# SensorController.net
KiCad netlist of a schematic drawn in EAGLE
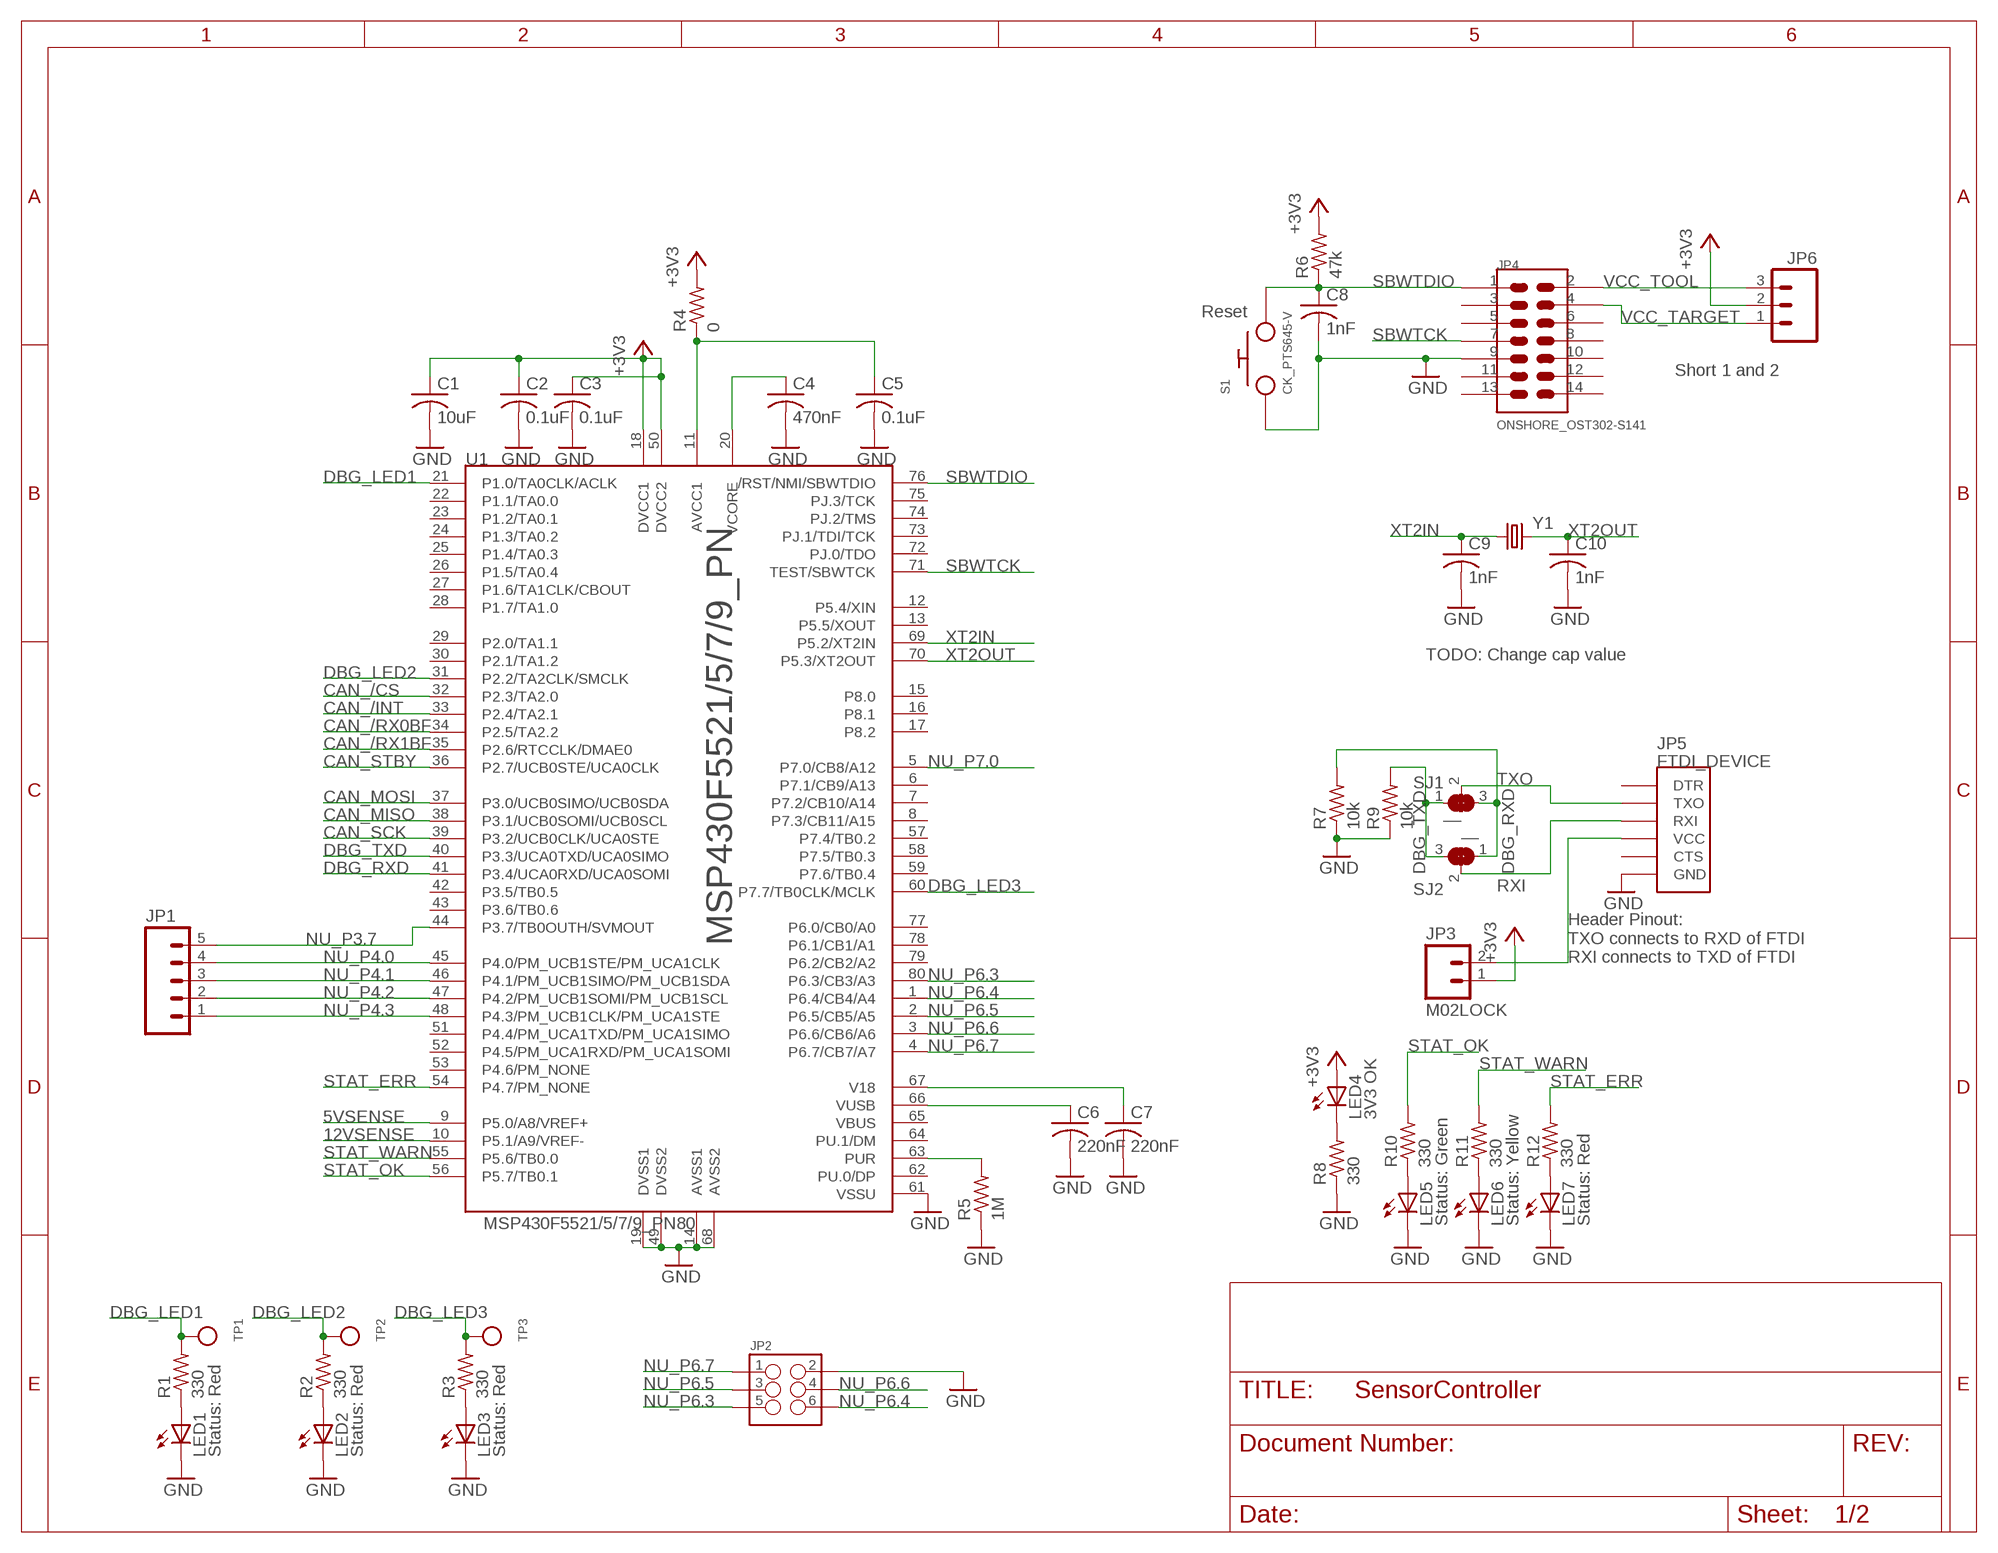
[diagram p0: schematic, sheet 1]
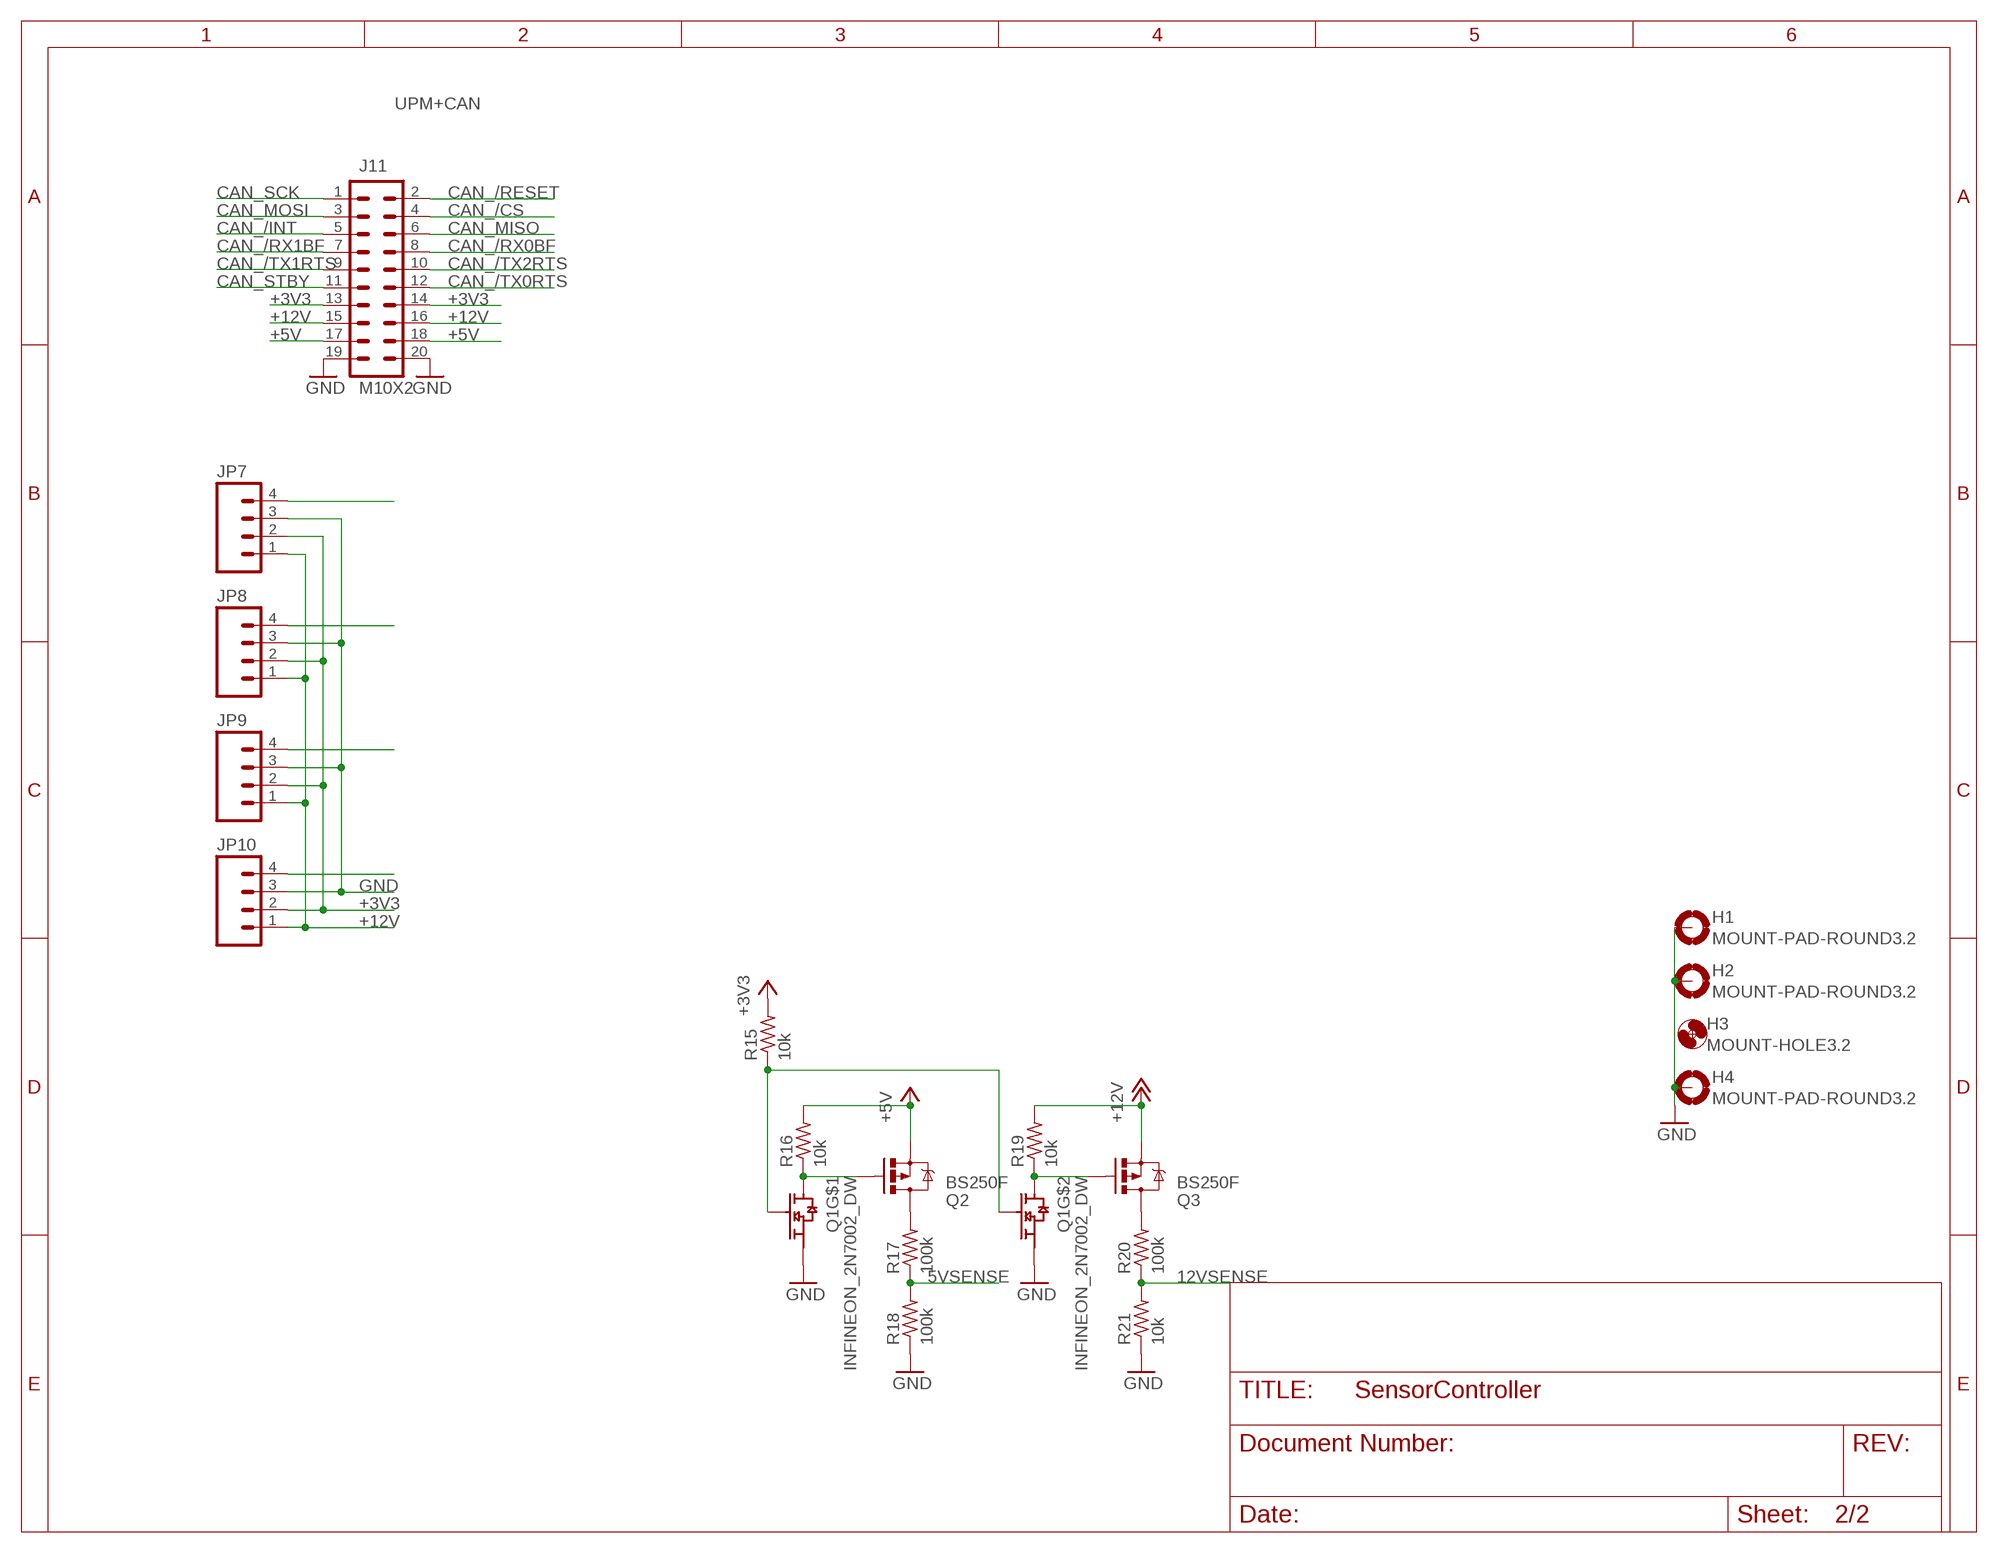
[diagram p1: schematic, sheet 2]

(export (version "E")
  (design (tool "Eeschema 10.0.6"))
  (components
    (comp (ref "H1")
      (value "MOUNT-PAD-ROUND3.2")
      (footprint "eagle-import:3,2-PAD")
      (libsource (lib "eagle-import") (part "MOUNT-PAD-ROUND3.2"))
    )
    (comp (ref "H2")
      (value "MOUNT-PAD-ROUND3.2")
      (footprint "eagle-import:3,2-PAD")
      (libsource (lib "eagle-import") (part "MOUNT-PAD-ROUND3.2"))
    )
    (comp (ref "H3")
      (value "MOUNT-HOLE3.2")
      (footprint "eagle-import:3,2")
      (libsource (lib "eagle-import") (part "MOUNT-HOLE3.2"))
    )
    (comp (ref "H4")
      (value "MOUNT-PAD-ROUND3.2")
      (footprint "eagle-import:3,2-PAD")
      (libsource (lib "eagle-import") (part "MOUNT-PAD-ROUND3.2"))
    )
    (comp (ref "J11")
      (value "M10X2")
      (footprint "eagle-import:2X10")
      (libsource (lib "eagle-import") (part "M10X2"))
    )
    (comp (ref "JP7")
      (value "M04PTH")
      (footprint "eagle-import:1X04")
      (libsource (lib "eagle-import") (part "M04PTH"))
    )
    (comp (ref "JP8")
      (value "M04PTH")
      (footprint "eagle-import:1X04")
      (libsource (lib "eagle-import") (part "M04PTH"))
    )
    (comp (ref "JP9")
      (value "M04PTH")
      (footprint "eagle-import:1X04")
      (libsource (lib "eagle-import") (part "M04PTH"))
    )
    (comp (ref "JP10")
      (value "M04PTH")
      (footprint "eagle-import:1X04")
      (libsource (lib "eagle-import") (part "M04PTH"))
    )
    (comp (ref "Q1")
      (value "INFINEON_2N7002_DW")
      (footprint "eagle-import:INFINEON_SOT363")
      (libsource (lib "eagle-import") (part "INFINEON_2N7002_DW"))
    )
    (comp (ref "Q2")
      (value "BS250F")
      (footprint "eagle-import:SOT23-3")
      (libsource (lib "eagle-import") (part "MOSFET-PCHANNELSMD"))
    )
    (comp (ref "Q3")
      (value "BS250F")
      (footprint "eagle-import:SOT23-3")
      (libsource (lib "eagle-import") (part "MOSFET-PCHANNELSMD"))
    )
    (comp (ref "R15")
      (value "10k")
      (footprint "eagle-import:R0603")
      (libsource (lib "eagle-import") (part "R-US_R0603"))
    )
    (comp (ref "R16")
      (value "10k")
      (footprint "eagle-import:R0603")
      (libsource (lib "eagle-import") (part "R-US_R0603"))
    )
    (comp (ref "R17")
      (value "100k")
      (footprint "eagle-import:R0603")
      (libsource (lib "eagle-import") (part "R-US_R0603"))
    )
    (comp (ref "R18")
      (value "100k")
      (footprint "eagle-import:R0603")
      (libsource (lib "eagle-import") (part "R-US_R0603"))
    )
    (comp (ref "R19")
      (value "10k")
      (footprint "eagle-import:R0603")
      (libsource (lib "eagle-import") (part "R-US_R0603"))
    )
    (comp (ref "R20")
      (value "100k")
      (footprint "eagle-import:R0603")
      (libsource (lib "eagle-import") (part "R-US_R0603"))
    )
    (comp (ref "R21")
      (value "10k")
      (footprint "eagle-import:R0603")
      (libsource (lib "eagle-import") (part "R-US_R0603"))
    )
    (comp (ref "C1")
      (value "10uF")
      (footprint "eagle-import:C0805")
      (libsource (lib "eagle-import") (part "C-USC0805"))
    )
    (comp (ref "C2")
      (value "0.1uF")
      (footprint "eagle-import:C0603")
      (libsource (lib "eagle-import") (part "C-USC0603"))
    )
    (comp (ref "C3")
      (value "0.1uF")
      (footprint "eagle-import:C0603")
      (libsource (lib "eagle-import") (part "C-USC0603"))
    )
    (comp (ref "C4")
      (value "470nF")
      (footprint "eagle-import:C0603")
      (libsource (lib "eagle-import") (part "C-USC0603"))
    )
    (comp (ref "C5")
      (value "0.1uF")
      (footprint "eagle-import:C0603")
      (libsource (lib "eagle-import") (part "C-USC0603"))
    )
    (comp (ref "C6")
      (value "220nF")
      (footprint "eagle-import:C0603")
      (libsource (lib "eagle-import") (part "C-USC0603"))
    )
    (comp (ref "C7")
      (value "220nF")
      (footprint "eagle-import:C0603")
      (libsource (lib "eagle-import") (part "C-USC0603"))
    )
    (comp (ref "C8")
      (value "1nF")
      (footprint "eagle-import:C0603")
      (libsource (lib "eagle-import") (part "C-USC0603"))
    )
    (comp (ref "C9")
      (value "1nF")
      (footprint "eagle-import:C0603")
      (libsource (lib "eagle-import") (part "C-USC0603"))
    )
    (comp (ref "C10")
      (value "1nF")
      (footprint "eagle-import:C0603")
      (libsource (lib "eagle-import") (part "C-USC0603"))
    )
    (comp (ref "JP1")
      (value "M05PTH")
      (footprint "eagle-import:1X05")
      (libsource (lib "eagle-import") (part "M05PTH"))
    )
    (comp (ref "JP2")
      (value "M03X22X3_SILK_SM")
      (footprint "eagle-import:2X3")
      (libsource (lib "eagle-import") (part "M03X22X3_SILK_SM"))
    )
    (comp (ref "JP3")
      (value "M02LOCK")
      (footprint "eagle-import:1X02_LOCK")
      (libsource (lib "eagle-import") (part "M02LOCK"))
    )
    (comp (ref "JP4")
      (value "ONSHORE_OST302-S141")
      (footprint "eagle-import:ONSHORE_OST302-S141")
      (libsource (lib "eagle-import") (part "ONSHORE_OST302-S141"))
    )
    (comp (ref "JP5")
      (value "FTDI_DEVICE")
      (footprint "eagle-import:FTDI_DEVICE_SIDE")
      (libsource (lib "eagle-import") (part "FTDI_DEVICE"))
    )
    (comp (ref "JP6")
      (value "M03LOCK")
      (footprint "eagle-import:1X03_LOCK")
      (libsource (lib "eagle-import") (part "M03LOCK"))
    )
    (comp (ref "LED1")
      (value "Status: Red")
      (footprint "eagle-import:LED-0603")
      (libsource (lib "eagle-import") (part "LED0603"))
    )
    (comp (ref "LED2")
      (value "Status: Red")
      (footprint "eagle-import:LED-0603")
      (libsource (lib "eagle-import") (part "LED0603"))
    )
    (comp (ref "LED3")
      (value "Status: Red")
      (footprint "eagle-import:LED-0603")
      (libsource (lib "eagle-import") (part "LED0603"))
    )
    (comp (ref "LED4")
      (value "3V3 OK")
      (footprint "eagle-import:LED-0603")
      (libsource (lib "eagle-import") (part "LED0603"))
    )
    (comp (ref "LED5")
      (value "Status: Green")
      (footprint "eagle-import:LED-0603")
      (libsource (lib "eagle-import") (part "LED0603"))
    )
    (comp (ref "LED6")
      (value "Status: Yellow")
      (footprint "eagle-import:LED-0603")
      (libsource (lib "eagle-import") (part "LED0603"))
    )
    (comp (ref "LED7")
      (value "Status: Red")
      (footprint "eagle-import:LED-0603")
      (libsource (lib "eagle-import") (part "LED0603"))
    )
    (comp (ref "R1")
      (value "330")
      (footprint "eagle-import:R0603")
      (libsource (lib "eagle-import") (part "R-US_R0603"))
    )
    (comp (ref "R2")
      (value "330")
      (footprint "eagle-import:R0603")
      (libsource (lib "eagle-import") (part "R-US_R0603"))
    )
    (comp (ref "R3")
      (value "330")
      (footprint "eagle-import:R0603")
      (libsource (lib "eagle-import") (part "R-US_R0603"))
    )
    (comp (ref "R4")
      (value "0")
      (footprint "eagle-import:R0603")
      (libsource (lib "eagle-import") (part "R-US_R0603"))
    )
    (comp (ref "R5")
      (value "1M")
      (footprint "eagle-import:R0603")
      (libsource (lib "eagle-import") (part "R-US_R0603"))
    )
    (comp (ref "R6")
      (value "47k")
      (footprint "eagle-import:R0603")
      (libsource (lib "eagle-import") (part "R-US_R0603"))
    )
    (comp (ref "R7")
      (value "10k")
      (footprint "eagle-import:R0603")
      (libsource (lib "eagle-import") (part "R-US_R0603"))
    )
    (comp (ref "R8")
      (value "330")
      (footprint "eagle-import:R0603")
      (libsource (lib "eagle-import") (part "R-US_R0603"))
    )
    (comp (ref "R9")
      (value "10k")
      (footprint "eagle-import:R0603")
      (libsource (lib "eagle-import") (part "R-US_R0603"))
    )
    (comp (ref "R10")
      (value "330")
      (footprint "eagle-import:R0603")
      (libsource (lib "eagle-import") (part "R-US_R0603"))
    )
    (comp (ref "R11")
      (value "330")
      (footprint "eagle-import:R0603")
      (libsource (lib "eagle-import") (part "R-US_R0603"))
    )
    (comp (ref "R12")
      (value "330")
      (footprint "eagle-import:R0603")
      (libsource (lib "eagle-import") (part "R-US_R0603"))
    )
    (comp (ref "S1")
      (value "CK_PTS645-V")
      (footprint "eagle-import:CK_PTS645-V")
      (libsource (lib "eagle-import") (part "CK_PTS645-V"))
    )
    (comp (ref "SJ1")
      (value "SOLDERJUMPER_2WAY0603")
      (footprint "eagle-import:SOLDERJUMPER_2WAY_OPEN_0603")
      (libsource (lib "eagle-import") (part "SOLDERJUMPER_2WAY0603"))
    )
    (comp (ref "SJ2")
      (value "SOLDERJUMPER_2WAY0603")
      (footprint "eagle-import:SOLDERJUMPER_2WAY_OPEN_0603")
      (libsource (lib "eagle-import") (part "SOLDERJUMPER_2WAY0603"))
    )
    (comp (ref "TP1")
      (value "TESTPOINT0.1\"")
      (footprint "eagle-import:1X01_ROUND")
      (libsource (lib "eagle-import") (part "TESTPOINT0.1{dblquote}"))
    )
    (comp (ref "TP2")
      (value "TESTPOINT0.1\"")
      (footprint "eagle-import:1X01_ROUND")
      (libsource (lib "eagle-import") (part "TESTPOINT0.1{dblquote}"))
    )
    (comp (ref "TP3")
      (value "TESTPOINT0.1\"")
      (footprint "eagle-import:1X01_ROUND")
      (libsource (lib "eagle-import") (part "TESTPOINT0.1{dblquote}"))
    )
    (comp (ref "U1")
      (value "MSP430F5521/5/7/9_PN80")
      (footprint "eagle-import:PN80")
      (libsource (lib "eagle-import") (part "MSP430F5521/5/7/9_PN80"))
    )
    (comp (ref "Y1")
      (value "CRYSTALHC49UV")
      (footprint "eagle-import:HC49U-V")
      (libsource (lib "eagle-import") (part "CRYSTALHC49UV"))
    )
  )
  (nets
    (net (code "1") (name "+3V3") (class "Default")
      (node (ref "C1") (pin "1") (pinfunction "1_1") (pintype "passive"))
      (node (ref "C2") (pin "1") (pinfunction "1_1") (pintype "passive"))
      (node (ref "C3") (pin "1") (pinfunction "1_1") (pintype "passive"))
      (node (ref "J11") (pin "13") (pinfunction "13_13") (pintype "passive"))
      (node (ref "J11") (pin "14") (pinfunction "14_14") (pintype "passive"))
      (node (ref "JP10") (pin "2") (pinfunction "2_2") (pintype "passive"))
      (node (ref "JP3") (pin "1") (pinfunction "1_1") (pintype "passive"))
      (node (ref "JP6") (pin "2") (pinfunction "2_2") (pintype "passive"))
      (node (ref "JP7") (pin "2") (pinfunction "2_2") (pintype "passive"))
      (node (ref "JP8") (pin "2") (pinfunction "2_2") (pintype "passive"))
      (node (ref "JP9") (pin "2") (pinfunction "2_2") (pintype "passive"))
      (node (ref "LED4") (pin "A") (pinfunction "A_A") (pintype "passive"))
      (node (ref "R15") (pin "2") (pinfunction "2_2") (pintype "passive"))
      (node (ref "R4") (pin "2") (pinfunction "2_2") (pintype "passive"))
      (node (ref "R6") (pin "2") (pinfunction "2_2") (pintype "passive"))
      (node (ref "U1") (pin "18") (pinfunction "DVCC1_18") (pintype "bidirectional"))
      (node (ref "U1") (pin "50") (pinfunction "DVCC2_50") (pintype "bidirectional"))
    )
    (net (code "2") (name "+5V") (class "Default")
      (node (ref "J11") (pin "17") (pinfunction "17_17") (pintype "passive"))
      (node (ref "J11") (pin "18") (pinfunction "18_18") (pintype "passive"))
      (node (ref "Q2") (pin "2") (pinfunction "S_2") (pintype "passive"))
      (node (ref "R16") (pin "2") (pinfunction "2_2") (pintype "passive"))
    )
    (net (code "3") (name "+12V") (class "Default")
      (node (ref "J11") (pin "15") (pinfunction "15_15") (pintype "passive"))
      (node (ref "J11") (pin "16") (pinfunction "16_16") (pintype "passive"))
      (node (ref "JP10") (pin "1") (pinfunction "1_1") (pintype "passive"))
      (node (ref "JP7") (pin "1") (pinfunction "1_1") (pintype "passive"))
      (node (ref "JP8") (pin "1") (pinfunction "1_1") (pintype "passive"))
      (node (ref "JP9") (pin "1") (pinfunction "1_1") (pintype "passive"))
      (node (ref "Q3") (pin "2") (pinfunction "S_2") (pintype "passive"))
      (node (ref "R19") (pin "2") (pinfunction "2_2") (pintype "passive"))
    )
    (net (code "4") (name "5VSENSE") (class "Default")
      (node (ref "R17") (pin "1") (pinfunction "1_1") (pintype "passive"))
      (node (ref "R18") (pin "2") (pinfunction "2_2") (pintype "passive"))
      (node (ref "U1") (pin "9") (pinfunction "P5.0/A8/VREF+_9") (pintype "bidirectional"))
    )
    (net (code "5") (name "12VSENSE") (class "Default")
      (node (ref "R20") (pin "1") (pinfunction "1_1") (pintype "passive"))
      (node (ref "R21") (pin "2") (pinfunction "2_2") (pintype "passive"))
      (node (ref "U1") (pin "10") (pinfunction "P5.1/A9/VREF-_10") (pintype "bidirectional"))
    )
    (net (code "6") (name "CAN_MISO") (class "Default")
      (node (ref "J11") (pin "6") (pinfunction "6_6") (pintype "passive"))
      (node (ref "U1") (pin "38") (pinfunction "P3.1/UCB0SOMI/UCB0SCL_38") (pintype "bidirectional"))
    )
    (net (code "7") (name "CAN_MOSI") (class "Default")
      (node (ref "J11") (pin "3") (pinfunction "3_3") (pintype "passive"))
      (node (ref "U1") (pin "37") (pinfunction "P3.0/UCB0SIMO/UCB0SDA_37") (pintype "bidirectional"))
    )
    (net (code "8") (name "CAN_SCK") (class "Default")
      (node (ref "J11") (pin "1") (pinfunction "1_1") (pintype "passive"))
      (node (ref "U1") (pin "39") (pinfunction "P3.2/UCB0CLK/UCA0STE_39") (pintype "bidirectional"))
    )
    (net (code "9") (name "CAN_STBY") (class "Default")
      (node (ref "J11") (pin "11") (pinfunction "11_11") (pintype "passive"))
      (node (ref "U1") (pin "36") (pinfunction "P2.7/UCB0STE/UCA0CLK_36") (pintype "bidirectional"))
    )
    (net (code "10") (name "CAN_{slash}CS") (class "Default")
      (node (ref "J11") (pin "4") (pinfunction "4_4") (pintype "passive"))
      (node (ref "U1") (pin "32") (pinfunction "P2.3/TA2.0_32") (pintype "bidirectional"))
    )
    (net (code "11") (name "CAN_{slash}INT") (class "Default")
      (node (ref "J11") (pin "5") (pinfunction "5_5") (pintype "passive"))
      (node (ref "U1") (pin "33") (pinfunction "P2.4/TA2.1_33") (pintype "bidirectional"))
    )
    (net (code "12") (name "CAN_{slash}RESET") (class "Default")
      (node (ref "J11") (pin "2") (pinfunction "2_2") (pintype "passive"))
    )
    (net (code "13") (name "CAN_{slash}RX0BF") (class "Default")
      (node (ref "J11") (pin "8") (pinfunction "8_8") (pintype "passive"))
      (node (ref "U1") (pin "34") (pinfunction "P2.5/TA2.2_34") (pintype "bidirectional"))
    )
    (net (code "14") (name "CAN_{slash}RX1BF") (class "Default")
      (node (ref "J11") (pin "7") (pinfunction "7_7") (pintype "passive"))
      (node (ref "U1") (pin "35") (pinfunction "P2.6/RTCCLK/DMAE0_35") (pintype "bidirectional"))
    )
    (net (code "15") (name "CAN_{slash}TX0RTS") (class "Default")
      (node (ref "J11") (pin "12") (pinfunction "12_12") (pintype "passive"))
    )
    (net (code "16") (name "CAN_{slash}TX1RTS") (class "Default")
      (node (ref "J11") (pin "9") (pinfunction "9_9") (pintype "passive"))
    )
    (net (code "17") (name "CAN_{slash}TX2RTS") (class "Default")
      (node (ref "J11") (pin "10") (pinfunction "10_10") (pintype "passive"))
    )
    (net (code "18") (name "DBG_LED1") (class "Default")
      (node (ref "R1") (pin "2") (pinfunction "2_2") (pintype "passive"))
      (node (ref "TP1") (pin "1") (pinfunction "P$1_1") (pintype "bidirectional"))
      (node (ref "U1") (pin "21") (pinfunction "P1.0/TA0CLK/ACLK_21") (pintype "bidirectional"))
    )
    (net (code "19") (name "DBG_LED2") (class "Default")
      (node (ref "R2") (pin "2") (pinfunction "2_2") (pintype "passive"))
      (node (ref "TP2") (pin "1") (pinfunction "P$1_1") (pintype "bidirectional"))
      (node (ref "U1") (pin "31") (pinfunction "P2.2/TA2CLK/SMCLK_31") (pintype "bidirectional"))
    )
    (net (code "20") (name "DBG_LED3") (class "Default")
      (node (ref "R3") (pin "2") (pinfunction "2_2") (pintype "passive"))
      (node (ref "TP3") (pin "1") (pinfunction "P$1_1") (pintype "bidirectional"))
      (node (ref "U1") (pin "60") (pinfunction "P7.7/TB0CLK/MCLK_60") (pintype "bidirectional"))
    )
    (net (code "21") (name "DBG_RXD") (class "Default")
      (node (ref "R7") (pin "2") (pinfunction "2_2") (pintype "passive"))
      (node (ref "SJ1") (pin "3") (pinfunction "3_3") (pintype "passive"))
      (node (ref "SJ2") (pin "1") (pinfunction "1_1") (pintype "passive"))
      (node (ref "U1") (pin "41") (pinfunction "P3.4/UCA0RXD/UCA0SOMI_41") (pintype "bidirectional"))
    )
    (net (code "22") (name "DBG_TXD") (class "Default")
      (node (ref "R9") (pin "2") (pinfunction "2_2") (pintype "passive"))
      (node (ref "SJ1") (pin "1") (pinfunction "1_1") (pintype "passive"))
      (node (ref "SJ2") (pin "3") (pinfunction "3_3") (pintype "passive"))
      (node (ref "U1") (pin "40") (pinfunction "P3.3/UCA0TXD/UCA0SIMO_40") (pintype "bidirectional"))
    )
    (net (code "23") (name "GND") (class "Default")
      (node (ref "C1") (pin "2") (pinfunction "2_2") (pintype "passive"))
      (node (ref "C10") (pin "2") (pinfunction "2_2") (pintype "passive"))
      (node (ref "C2") (pin "2") (pinfunction "2_2") (pintype "passive"))
      (node (ref "C3") (pin "2") (pinfunction "2_2") (pintype "passive"))
      (node (ref "C4") (pin "2") (pinfunction "2_2") (pintype "passive"))
      (node (ref "C5") (pin "2") (pinfunction "2_2") (pintype "passive"))
      (node (ref "C6") (pin "2") (pinfunction "2_2") (pintype "passive"))
      (node (ref "C7") (pin "2") (pinfunction "2_2") (pintype "passive"))
      (node (ref "C8") (pin "2") (pinfunction "2_2") (pintype "passive"))
      (node (ref "C9") (pin "2") (pinfunction "2_2") (pintype "passive"))
      (node (ref "H1") (pin "B3,2") (pinfunction "MOUNT_B3,2") (pintype "passive"))
      (node (ref "H2") (pin "B3,2") (pinfunction "MOUNT_B3,2") (pintype "passive"))
      (node (ref "H4") (pin "B3,2") (pinfunction "MOUNT_B3,2") (pintype "passive"))
      (node (ref "J11") (pin "19") (pinfunction "19_19") (pintype "passive"))
      (node (ref "J11") (pin "20") (pinfunction "20_20") (pintype "passive"))
      (node (ref "JP10") (pin "3") (pinfunction "3_3") (pintype "passive"))
      (node (ref "JP2") (pin "2") (pinfunction "2_2") (pintype "bidirectional"))
      (node (ref "JP4") (pin "9") (pinfunction "9_9") (pintype "bidirectional"))
      (node (ref "JP5") (pin "P$6") (pinfunction "GND_P$6") (pintype "bidirectional"))
      (node (ref "JP7") (pin "3") (pinfunction "3_3") (pintype "passive"))
      (node (ref "JP8") (pin "3") (pinfunction "3_3") (pintype "passive"))
      (node (ref "JP9") (pin "3") (pinfunction "3_3") (pintype "passive"))
      (node (ref "LED1") (pin "C") (pinfunction "C_C") (pintype "passive"))
      (node (ref "LED2") (pin "C") (pinfunction "C_C") (pintype "passive"))
      (node (ref "LED3") (pin "C") (pinfunction "C_C") (pintype "passive"))
      (node (ref "LED5") (pin "C") (pinfunction "C_C") (pintype "passive"))
      (node (ref "LED6") (pin "C") (pinfunction "C_C") (pintype "passive"))
      (node (ref "LED7") (pin "C") (pinfunction "C_C") (pintype "passive"))
      (node (ref "Q1") (pin "1") (pinfunction "SOURCE_1") (pintype "bidirectional"))
      (node (ref "Q1") (pin "4") (pinfunction "SOURCE_4") (pintype "bidirectional"))
      (node (ref "R18") (pin "1") (pinfunction "1_1") (pintype "passive"))
      (node (ref "R21") (pin "1") (pinfunction "1_1") (pintype "passive"))
      (node (ref "R5") (pin "1") (pinfunction "1_1") (pintype "passive"))
      (node (ref "R7") (pin "1") (pinfunction "1_1") (pintype "passive"))
      (node (ref "R8") (pin "1") (pinfunction "1_1") (pintype "passive"))
      (node (ref "R9") (pin "1") (pinfunction "1_1") (pintype "passive"))
      (node (ref "S1") (pin "1") (pinfunction "1_1") (pintype "bidirectional"))
      (node (ref "U1") (pin "14") (pinfunction "AVSS1_14") (pintype "bidirectional"))
      (node (ref "U1") (pin "19") (pinfunction "DVSS1_19") (pintype "bidirectional"))
      (node (ref "U1") (pin "49") (pinfunction "DVSS2_49") (pintype "bidirectional"))
      (node (ref "U1") (pin "61") (pinfunction "VSSU_61") (pintype "bidirectional"))
      (node (ref "U1") (pin "68") (pinfunction "AVSS2_68") (pintype "bidirectional"))
    )
    (net (code "24") (name "NU_P3.7") (class "Default")
      (node (ref "JP1") (pin "5") (pinfunction "5_5") (pintype "passive"))
      (node (ref "U1") (pin "44") (pinfunction "P3.7/TB0OUTH/SVMOUT_44") (pintype "bidirectional"))
    )
    (net (code "25") (name "NU_P4.0") (class "Default")
      (node (ref "JP1") (pin "4") (pinfunction "4_4") (pintype "passive"))
      (node (ref "U1") (pin "45") (pinfunction "P4.0/PM_UCB1STE/PM_UCA1CLK_45") (pintype "bidirectional"))
    )
    (net (code "26") (name "NU_P4.1") (class "Default")
      (node (ref "JP1") (pin "3") (pinfunction "3_3") (pintype "passive"))
      (node (ref "U1") (pin "46") (pinfunction "P4.1/PM_UCB1SIMO/PM_UCB1SDA_46") (pintype "bidirectional"))
    )
    (net (code "27") (name "NU_P4.2") (class "Default")
      (node (ref "JP1") (pin "2") (pinfunction "2_2") (pintype "passive"))
      (node (ref "U1") (pin "47") (pinfunction "P4.2/PM_UCB1SOMI/PM_UCB1SCL_47") (pintype "bidirectional"))
    )
    (net (code "28") (name "NU_P4.3") (class "Default")
      (node (ref "JP1") (pin "1") (pinfunction "1_1") (pintype "passive"))
      (node (ref "U1") (pin "48") (pinfunction "P4.3/PM_UCB1CLK/PM_UCA1STE_48") (pintype "bidirectional"))
    )
    (net (code "29") (name "NU_P6.3") (class "Default")
      (node (ref "JP2") (pin "5") (pinfunction "5_5") (pintype "bidirectional"))
      (node (ref "U1") (pin "80") (pinfunction "P6.3/CB3/A3_80") (pintype "bidirectional"))
    )
    (net (code "30") (name "NU_P6.4") (class "Default")
      (node (ref "JP2") (pin "6") (pinfunction "6_6") (pintype "bidirectional"))
      (node (ref "U1") (pin "1") (pinfunction "P6.4/CB4/A4_1") (pintype "bidirectional"))
    )
    (net (code "31") (name "NU_P6.5") (class "Default")
      (node (ref "JP2") (pin "3") (pinfunction "3_3") (pintype "bidirectional"))
      (node (ref "U1") (pin "2") (pinfunction "P6.5/CB5/A5_2") (pintype "bidirectional"))
    )
    (net (code "32") (name "NU_P6.6") (class "Default")
      (node (ref "JP2") (pin "4") (pinfunction "4_4") (pintype "bidirectional"))
      (node (ref "U1") (pin "3") (pinfunction "P6.6/CB6/A6_3") (pintype "bidirectional"))
    )
    (net (code "33") (name "NU_P6.7") (class "Default")
      (node (ref "JP2") (pin "1") (pinfunction "1_1") (pintype "bidirectional"))
      (node (ref "U1") (pin "4") (pinfunction "P6.7/CB7/A7_4") (pintype "bidirectional"))
    )
    (net (code "34") (name "NU_P7.0") (class "Default")
      (node (ref "U1") (pin "5") (pinfunction "P7.0/CB8/A12_5") (pintype "bidirectional"))
    )
    (net (code "35") (name "Net-(JP5-VCC)") (class "Default")
      (node (ref "JP3") (pin "2") (pinfunction "2_2") (pintype "passive"))
      (node (ref "JP5") (pin "P$4") (pinfunction "VCC_P$4") (pintype "bidirectional"))
    )
    (net (code "36") (name "Net-(LED1-PadA)") (class "Default")
      (node (ref "LED1") (pin "A") (pinfunction "A_A") (pintype "passive"))
      (node (ref "R1") (pin "1") (pinfunction "1_1") (pintype "passive"))
    )
    (net (code "37") (name "Net-(LED2-PadA)") (class "Default")
      (node (ref "LED2") (pin "A") (pinfunction "A_A") (pintype "passive"))
      (node (ref "R2") (pin "1") (pinfunction "1_1") (pintype "passive"))
    )
    (net (code "38") (name "Net-(LED3-PadA)") (class "Default")
      (node (ref "LED3") (pin "A") (pinfunction "A_A") (pintype "passive"))
      (node (ref "R3") (pin "1") (pinfunction "1_1") (pintype "passive"))
    )
    (net (code "39") (name "Net-(LED4-PadC)") (class "Default")
      (node (ref "LED4") (pin "C") (pinfunction "C_C") (pintype "passive"))
      (node (ref "R8") (pin "2") (pinfunction "2_2") (pintype "passive"))
    )
    (net (code "40") (name "Net-(LED5-PadA)") (class "Default")
      (node (ref "LED5") (pin "A") (pinfunction "A_A") (pintype "passive"))
      (node (ref "R10") (pin "1") (pinfunction "1_1") (pintype "passive"))
    )
    (net (code "41") (name "Net-(LED6-PadA)") (class "Default")
      (node (ref "LED6") (pin "A") (pinfunction "A_A") (pintype "passive"))
      (node (ref "R11") (pin "1") (pinfunction "1_1") (pintype "passive"))
    )
    (net (code "42") (name "Net-(LED7-PadA)") (class "Default")
      (node (ref "LED7") (pin "A") (pinfunction "A_A") (pintype "passive"))
      (node (ref "R12") (pin "1") (pinfunction "1_1") (pintype "passive"))
    )
    (net (code "43") (name "Net-(Q1A-DRAIN)") (class "Default")
      (node (ref "Q1") (pin "6") (pinfunction "DRAIN_6") (pintype "bidirectional"))
      (node (ref "Q2") (pin "1") (pinfunction "G_1") (pintype "passive"))
      (node (ref "R16") (pin "1") (pinfunction "1_1") (pintype "passive"))
    )
    (net (code "44") (name "Net-(Q1A-GATE)") (class "Default")
      (node (ref "Q1") (pin "2") (pinfunction "GATE_2") (pintype "bidirectional"))
      (node (ref "Q1") (pin "5") (pinfunction "GATE_5") (pintype "bidirectional"))
      (node (ref "R15") (pin "1") (pinfunction "1_1") (pintype "passive"))
    )
    (net (code "45") (name "Net-(Q1B-DRAIN)") (class "Default")
      (node (ref "Q1") (pin "3") (pinfunction "DRAIN_3") (pintype "bidirectional"))
      (node (ref "Q3") (pin "1") (pinfunction "G_1") (pintype "passive"))
      (node (ref "R19") (pin "1") (pinfunction "1_1") (pintype "passive"))
    )
    (net (code "46") (name "Net-(Q2-D)") (class "Default")
      (node (ref "Q2") (pin "3") (pinfunction "D_3") (pintype "passive"))
      (node (ref "R17") (pin "2") (pinfunction "2_2") (pintype "passive"))
    )
    (net (code "47") (name "Net-(Q3-D)") (class "Default")
      (node (ref "Q3") (pin "3") (pinfunction "D_3") (pintype "passive"))
      (node (ref "R20") (pin "2") (pinfunction "2_2") (pintype "passive"))
    )
    (net (code "48") (name "Net-(U1-AVCC1)") (class "Default")
      (node (ref "C5") (pin "1") (pinfunction "1_1") (pintype "passive"))
      (node (ref "R4") (pin "1") (pinfunction "1_1") (pintype "passive"))
      (node (ref "U1") (pin "11") (pinfunction "AVCC1_11") (pintype "bidirectional"))
    )
    (net (code "49") (name "Net-(U1-PUR)") (class "Default")
      (node (ref "R5") (pin "2") (pinfunction "2_2") (pintype "passive"))
      (node (ref "U1") (pin "63") (pinfunction "PUR_63") (pintype "bidirectional"))
    )
    (net (code "50") (name "Net-(U1-V18)") (class "Default")
      (node (ref "C7") (pin "1") (pinfunction "1_1") (pintype "passive"))
      (node (ref "U1") (pin "67") (pinfunction "V18_67") (pintype "bidirectional"))
    )
    (net (code "51") (name "Net-(U1-VCORE)") (class "Default")
      (node (ref "C4") (pin "1") (pinfunction "1_1") (pintype "passive"))
      (node (ref "U1") (pin "20") (pinfunction "VCORE_20") (pintype "bidirectional"))
    )
    (net (code "52") (name "Net-(U1-VUSB)") (class "Default")
      (node (ref "C6") (pin "1") (pinfunction "1_1") (pintype "passive"))
      (node (ref "U1") (pin "66") (pinfunction "VUSB_66") (pintype "bidirectional"))
    )
    (net (code "53") (name "RXI") (class "Default")
      (node (ref "JP5") (pin "P$3") (pinfunction "RXI_P$3") (pintype "bidirectional"))
      (node (ref "SJ2") (pin "2") (pinfunction "2_2") (pintype "passive"))
    )
    (net (code "54") (name "SBWTCK") (class "Default")
      (node (ref "JP4") (pin "7") (pinfunction "7_7") (pintype "bidirectional"))
      (node (ref "U1") (pin "71") (pinfunction "TEST/SBWTCK_71") (pintype "bidirectional"))
    )
    (net (code "55") (name "SBWTDIO") (class "Default")
      (node (ref "C8") (pin "1") (pinfunction "1_1") (pintype "passive"))
      (node (ref "JP4") (pin "1") (pinfunction "1_1") (pintype "bidirectional"))
      (node (ref "R6") (pin "1") (pinfunction "1_1") (pintype "passive"))
      (node (ref "S1") (pin "2") (pinfunction "2_2") (pintype "bidirectional"))
      (node (ref "U1") (pin "76") (pinfunction "/RST/NMI/SBWTDIO_76") (pintype "bidirectional"))
    )
    (net (code "56") (name "STAT_ERR") (class "Default")
      (node (ref "R12") (pin "2") (pinfunction "2_2") (pintype "passive"))
      (node (ref "U1") (pin "54") (pinfunction "P4.7/PM_NONE_54") (pintype "bidirectional"))
    )
    (net (code "57") (name "STAT_OK") (class "Default")
      (node (ref "R10") (pin "2") (pinfunction "2_2") (pintype "passive"))
      (node (ref "U1") (pin "56") (pinfunction "P5.7/TB0.1_56") (pintype "bidirectional"))
    )
    (net (code "58") (name "STAT_WARN") (class "Default")
      (node (ref "R11") (pin "2") (pinfunction "2_2") (pintype "passive"))
      (node (ref "U1") (pin "55") (pinfunction "P5.6/TB0.0_55") (pintype "bidirectional"))
    )
    (net (code "59") (name "TXO") (class "Default")
      (node (ref "JP5") (pin "P$2") (pinfunction "TXO_P$2") (pintype "bidirectional"))
      (node (ref "SJ1") (pin "2") (pinfunction "2_2") (pintype "passive"))
    )
    (net (code "60") (name "VCC_TARGET") (class "Default")
      (node (ref "JP4") (pin "4") (pinfunction "4_4") (pintype "bidirectional"))
      (node (ref "JP6") (pin "1") (pinfunction "1_1") (pintype "passive"))
    )
    (net (code "61") (name "VCC_TOOL") (class "Default")
      (node (ref "JP4") (pin "2") (pinfunction "2_2") (pintype "bidirectional"))
      (node (ref "JP6") (pin "3") (pinfunction "3_3") (pintype "passive"))
    )
    (net (code "62") (name "XT2IN") (class "Default")
      (node (ref "C9") (pin "1") (pinfunction "1_1") (pintype "passive"))
      (node (ref "U1") (pin "69") (pinfunction "P5.2/XT2IN_69") (pintype "bidirectional"))
      (node (ref "Y1") (pin "1") (pinfunction "1_1") (pintype "passive"))
    )
    (net (code "63") (name "XT2OUT") (class "Default")
      (node (ref "C10") (pin "1") (pinfunction "1_1") (pintype "passive"))
      (node (ref "U1") (pin "70") (pinfunction "P5.3/XT2OUT_70") (pintype "bidirectional"))
      (node (ref "Y1") (pin "2") (pinfunction "2_2") (pintype "passive"))
    )
    (net (code "64") (name "unconnected-(JP4-Pad3)") (class "Default")
      (node (ref "JP4") (pin "3") (pinfunction "3_3") (pintype "bidirectional"))
    )
    (net (code "65") (name "unconnected-(JP4-Pad5)") (class "Default")
      (node (ref "JP4") (pin "5") (pinfunction "5_5") (pintype "bidirectional"))
    )
    (net (code "66") (name "unconnected-(JP4-Pad6)") (class "Default")
      (node (ref "JP4") (pin "6") (pinfunction "6_6") (pintype "bidirectional"))
    )
    (net (code "67") (name "unconnected-(JP4-Pad8)") (class "Default")
      (node (ref "JP4") (pin "8") (pinfunction "8_8") (pintype "bidirectional"))
    )
    (net (code "68") (name "unconnected-(JP4-Pad10)") (class "Default")
      (node (ref "JP4") (pin "10") (pinfunction "10_10") (pintype "bidirectional"))
    )
    (net (code "69") (name "unconnected-(JP4-Pad11)") (class "Default")
      (node (ref "JP4") (pin "11") (pinfunction "11_11") (pintype "bidirectional"))
    )
    (net (code "70") (name "unconnected-(JP4-Pad12)") (class "Default")
      (node (ref "JP4") (pin "12") (pinfunction "12_12") (pintype "bidirectional"))
    )
    (net (code "71") (name "unconnected-(JP4-Pad13)") (class "Default")
      (node (ref "JP4") (pin "13") (pinfunction "13_13") (pintype "bidirectional"))
    )
    (net (code "72") (name "unconnected-(JP4-Pad14)") (class "Default")
      (node (ref "JP4") (pin "14") (pinfunction "14_14") (pintype "bidirectional"))
    )
    (net (code "73") (name "unconnected-(JP5-CTS-PadP$5)") (class "Default")
      (node (ref "JP5") (pin "P$5") (pinfunction "CTS_P$5") (pintype "bidirectional"))
    )
    (net (code "74") (name "unconnected-(JP5-DTR-PadP$1)") (class "Default")
      (node (ref "JP5") (pin "P$1") (pinfunction "DTR_P$1") (pintype "bidirectional"))
    )
    (net (code "75") (name "unconnected-(JP7-Pad4)") (class "Default")
      (node (ref "JP7") (pin "4") (pinfunction "4_4") (pintype "passive"))
    )
    (net (code "76") (name "unconnected-(JP8-Pad4)") (class "Default")
      (node (ref "JP8") (pin "4") (pinfunction "4_4") (pintype "passive"))
    )
    (net (code "77") (name "unconnected-(JP9-Pad4)") (class "Default")
      (node (ref "JP9") (pin "4") (pinfunction "4_4") (pintype "passive"))
    )
    (net (code "78") (name "unconnected-(JP10-Pad4)") (class "Default")
      (node (ref "JP10") (pin "4") (pinfunction "4_4") (pintype "passive"))
    )
    (net (code "79") (name "unconnected-(U1-P1.1{slash}TA0.0-Pad22)") (class "Default")
      (node (ref "U1") (pin "22") (pinfunction "P1.1/TA0.0_22") (pintype "bidirectional"))
    )
    (net (code "80") (name "unconnected-(U1-P1.2{slash}TA0.1-Pad23)") (class "Default")
      (node (ref "U1") (pin "23") (pinfunction "P1.2/TA0.1_23") (pintype "bidirectional"))
    )
    (net (code "81") (name "unconnected-(U1-P1.3{slash}TA0.2-Pad24)") (class "Default")
      (node (ref "U1") (pin "24") (pinfunction "P1.3/TA0.2_24") (pintype "bidirectional"))
    )
    (net (code "82") (name "unconnected-(U1-P1.4{slash}TA0.3-Pad25)") (class "Default")
      (node (ref "U1") (pin "25") (pinfunction "P1.4/TA0.3_25") (pintype "bidirectional"))
    )
    (net (code "83") (name "unconnected-(U1-P1.5{slash}TA0.4-Pad26)") (class "Default")
      (node (ref "U1") (pin "26") (pinfunction "P1.5/TA0.4_26") (pintype "bidirectional"))
    )
    (net (code "84") (name "unconnected-(U1-P1.6{slash}TA1CLK{slash}CBOUT-Pad27)") (class "Default")
      (node (ref "U1") (pin "27") (pinfunction "P1.6/TA1CLK/CBOUT_27") (pintype "bidirectional"))
    )
    (net (code "85") (name "unconnected-(U1-P1.7{slash}TA1.0-Pad28)") (class "Default")
      (node (ref "U1") (pin "28") (pinfunction "P1.7/TA1.0_28") (pintype "bidirectional"))
    )
    (net (code "86") (name "unconnected-(U1-P2.0{slash}TA1.1-Pad29)") (class "Default")
      (node (ref "U1") (pin "29") (pinfunction "P2.0/TA1.1_29") (pintype "bidirectional"))
    )
    (net (code "87") (name "unconnected-(U1-P2.1{slash}TA1.2-Pad30)") (class "Default")
      (node (ref "U1") (pin "30") (pinfunction "P2.1/TA1.2_30") (pintype "bidirectional"))
    )
    (net (code "88") (name "unconnected-(U1-P3.5{slash}TB0.5-Pad42)") (class "Default")
      (node (ref "U1") (pin "42") (pinfunction "P3.5/TB0.5_42") (pintype "bidirectional"))
    )
    (net (code "89") (name "unconnected-(U1-P3.6{slash}TB0.6-Pad43)") (class "Default")
      (node (ref "U1") (pin "43") (pinfunction "P3.6/TB0.6_43") (pintype "bidirectional"))
    )
    (net (code "90") (name "unconnected-(U1-P4.4{slash}PM_UCA1TXD{slash}PM_UCA1SIMO-Pad51)") (class "Default")
      (node (ref "U1") (pin "51") (pinfunction "P4.4/PM_UCA1TXD/PM_UCA1SIMO_51") (pintype "bidirectional"))
    )
    (net (code "91") (name "unconnected-(U1-P4.5{slash}PM_UCA1RXD{slash}PM_UCA1SOMI-Pad52)") (class "Default")
      (node (ref "U1") (pin "52") (pinfunction "P4.5/PM_UCA1RXD/PM_UCA1SOMI_52") (pintype "bidirectional"))
    )
    (net (code "92") (name "unconnected-(U1-P4.6{slash}PM_NONE-Pad53)") (class "Default")
      (node (ref "U1") (pin "53") (pinfunction "P4.6/PM_NONE_53") (pintype "bidirectional"))
    )
    (net (code "93") (name "unconnected-(U1-P5.4{slash}XIN-Pad12)") (class "Default")
      (node (ref "U1") (pin "12") (pinfunction "P5.4/XIN_12") (pintype "bidirectional"))
    )
    (net (code "94") (name "unconnected-(U1-P5.5{slash}XOUT-Pad13)") (class "Default")
      (node (ref "U1") (pin "13") (pinfunction "P5.5/XOUT_13") (pintype "bidirectional"))
    )
    (net (code "95") (name "unconnected-(U1-P6.0{slash}CB0{slash}A0-Pad77)") (class "Default")
      (node (ref "U1") (pin "77") (pinfunction "P6.0/CB0/A0_77") (pintype "bidirectional"))
    )
    (net (code "96") (name "unconnected-(U1-P6.1{slash}CB1{slash}A1-Pad78)") (class "Default")
      (node (ref "U1") (pin "78") (pinfunction "P6.1/CB1/A1_78") (pintype "bidirectional"))
    )
    (net (code "97") (name "unconnected-(U1-P6.2{slash}CB2{slash}A2-Pad79)") (class "Default")
      (node (ref "U1") (pin "79") (pinfunction "P6.2/CB2/A2_79") (pintype "bidirectional"))
    )
    (net (code "98") (name "unconnected-(U1-P7.1{slash}CB9{slash}A13-Pad6)") (class "Default")
      (node (ref "U1") (pin "6") (pinfunction "P7.1/CB9/A13_6") (pintype "bidirectional"))
    )
    (net (code "99") (name "unconnected-(U1-P7.2{slash}CB10{slash}A14-Pad7)") (class "Default")
      (node (ref "U1") (pin "7") (pinfunction "P7.2/CB10/A14_7") (pintype "bidirectional"))
    )
    (net (code "100") (name "unconnected-(U1-P7.3{slash}CB11{slash}A15-Pad8)") (class "Default")
      (node (ref "U1") (pin "8") (pinfunction "P7.3/CB11/A15_8") (pintype "bidirectional"))
    )
    (net (code "101") (name "unconnected-(U1-P7.4{slash}TB0.2-Pad57)") (class "Default")
      (node (ref "U1") (pin "57") (pinfunction "P7.4/TB0.2_57") (pintype "bidirectional"))
    )
    (net (code "102") (name "unconnected-(U1-P7.5{slash}TB0.3-Pad58)") (class "Default")
      (node (ref "U1") (pin "58") (pinfunction "P7.5/TB0.3_58") (pintype "bidirectional"))
    )
    (net (code "103") (name "unconnected-(U1-P7.6{slash}TB0.4-Pad59)") (class "Default")
      (node (ref "U1") (pin "59") (pinfunction "P7.6/TB0.4_59") (pintype "bidirectional"))
    )
    (net (code "104") (name "unconnected-(U1-P8.0-Pad15)") (class "Default")
      (node (ref "U1") (pin "15") (pinfunction "P8.0_15") (pintype "bidirectional"))
    )
    (net (code "105") (name "unconnected-(U1-P8.1-Pad16)") (class "Default")
      (node (ref "U1") (pin "16") (pinfunction "P8.1_16") (pintype "bidirectional"))
    )
    (net (code "106") (name "unconnected-(U1-P8.2-Pad17)") (class "Default")
      (node (ref "U1") (pin "17") (pinfunction "P8.2_17") (pintype "bidirectional"))
    )
    (net (code "107") (name "unconnected-(U1-PJ.0{slash}TDO-Pad72)") (class "Default")
      (node (ref "U1") (pin "72") (pinfunction "PJ.0/TDO_72") (pintype "bidirectional"))
    )
    (net (code "108") (name "unconnected-(U1-PJ.1{slash}TDI{slash}TCK-Pad73)") (class "Default")
      (node (ref "U1") (pin "73") (pinfunction "PJ.1/TDI/TCK_73") (pintype "bidirectional"))
    )
    (net (code "109") (name "unconnected-(U1-PJ.2{slash}TMS-Pad74)") (class "Default")
      (node (ref "U1") (pin "74") (pinfunction "PJ.2/TMS_74") (pintype "bidirectional"))
    )
    (net (code "110") (name "unconnected-(U1-PJ.3{slash}TCK-Pad75)") (class "Default")
      (node (ref "U1") (pin "75") (pinfunction "PJ.3/TCK_75") (pintype "bidirectional"))
    )
    (net (code "111") (name "unconnected-(U1-PU.0{slash}DP-Pad62)") (class "Default")
      (node (ref "U1") (pin "62") (pinfunction "PU.0/DP_62") (pintype "bidirectional"))
    )
    (net (code "112") (name "unconnected-(U1-PU.1{slash}DM-Pad64)") (class "Default")
      (node (ref "U1") (pin "64") (pinfunction "PU.1/DM_64") (pintype "bidirectional"))
    )
    (net (code "113") (name "unconnected-(U1-VBUS-Pad65)") (class "Default")
      (node (ref "U1") (pin "65") (pinfunction "VBUS_65") (pintype "bidirectional"))
    )
  )
)
